# Task_2021-05-29.net
KiCad netlist of a schematic drawn in EasyEDA
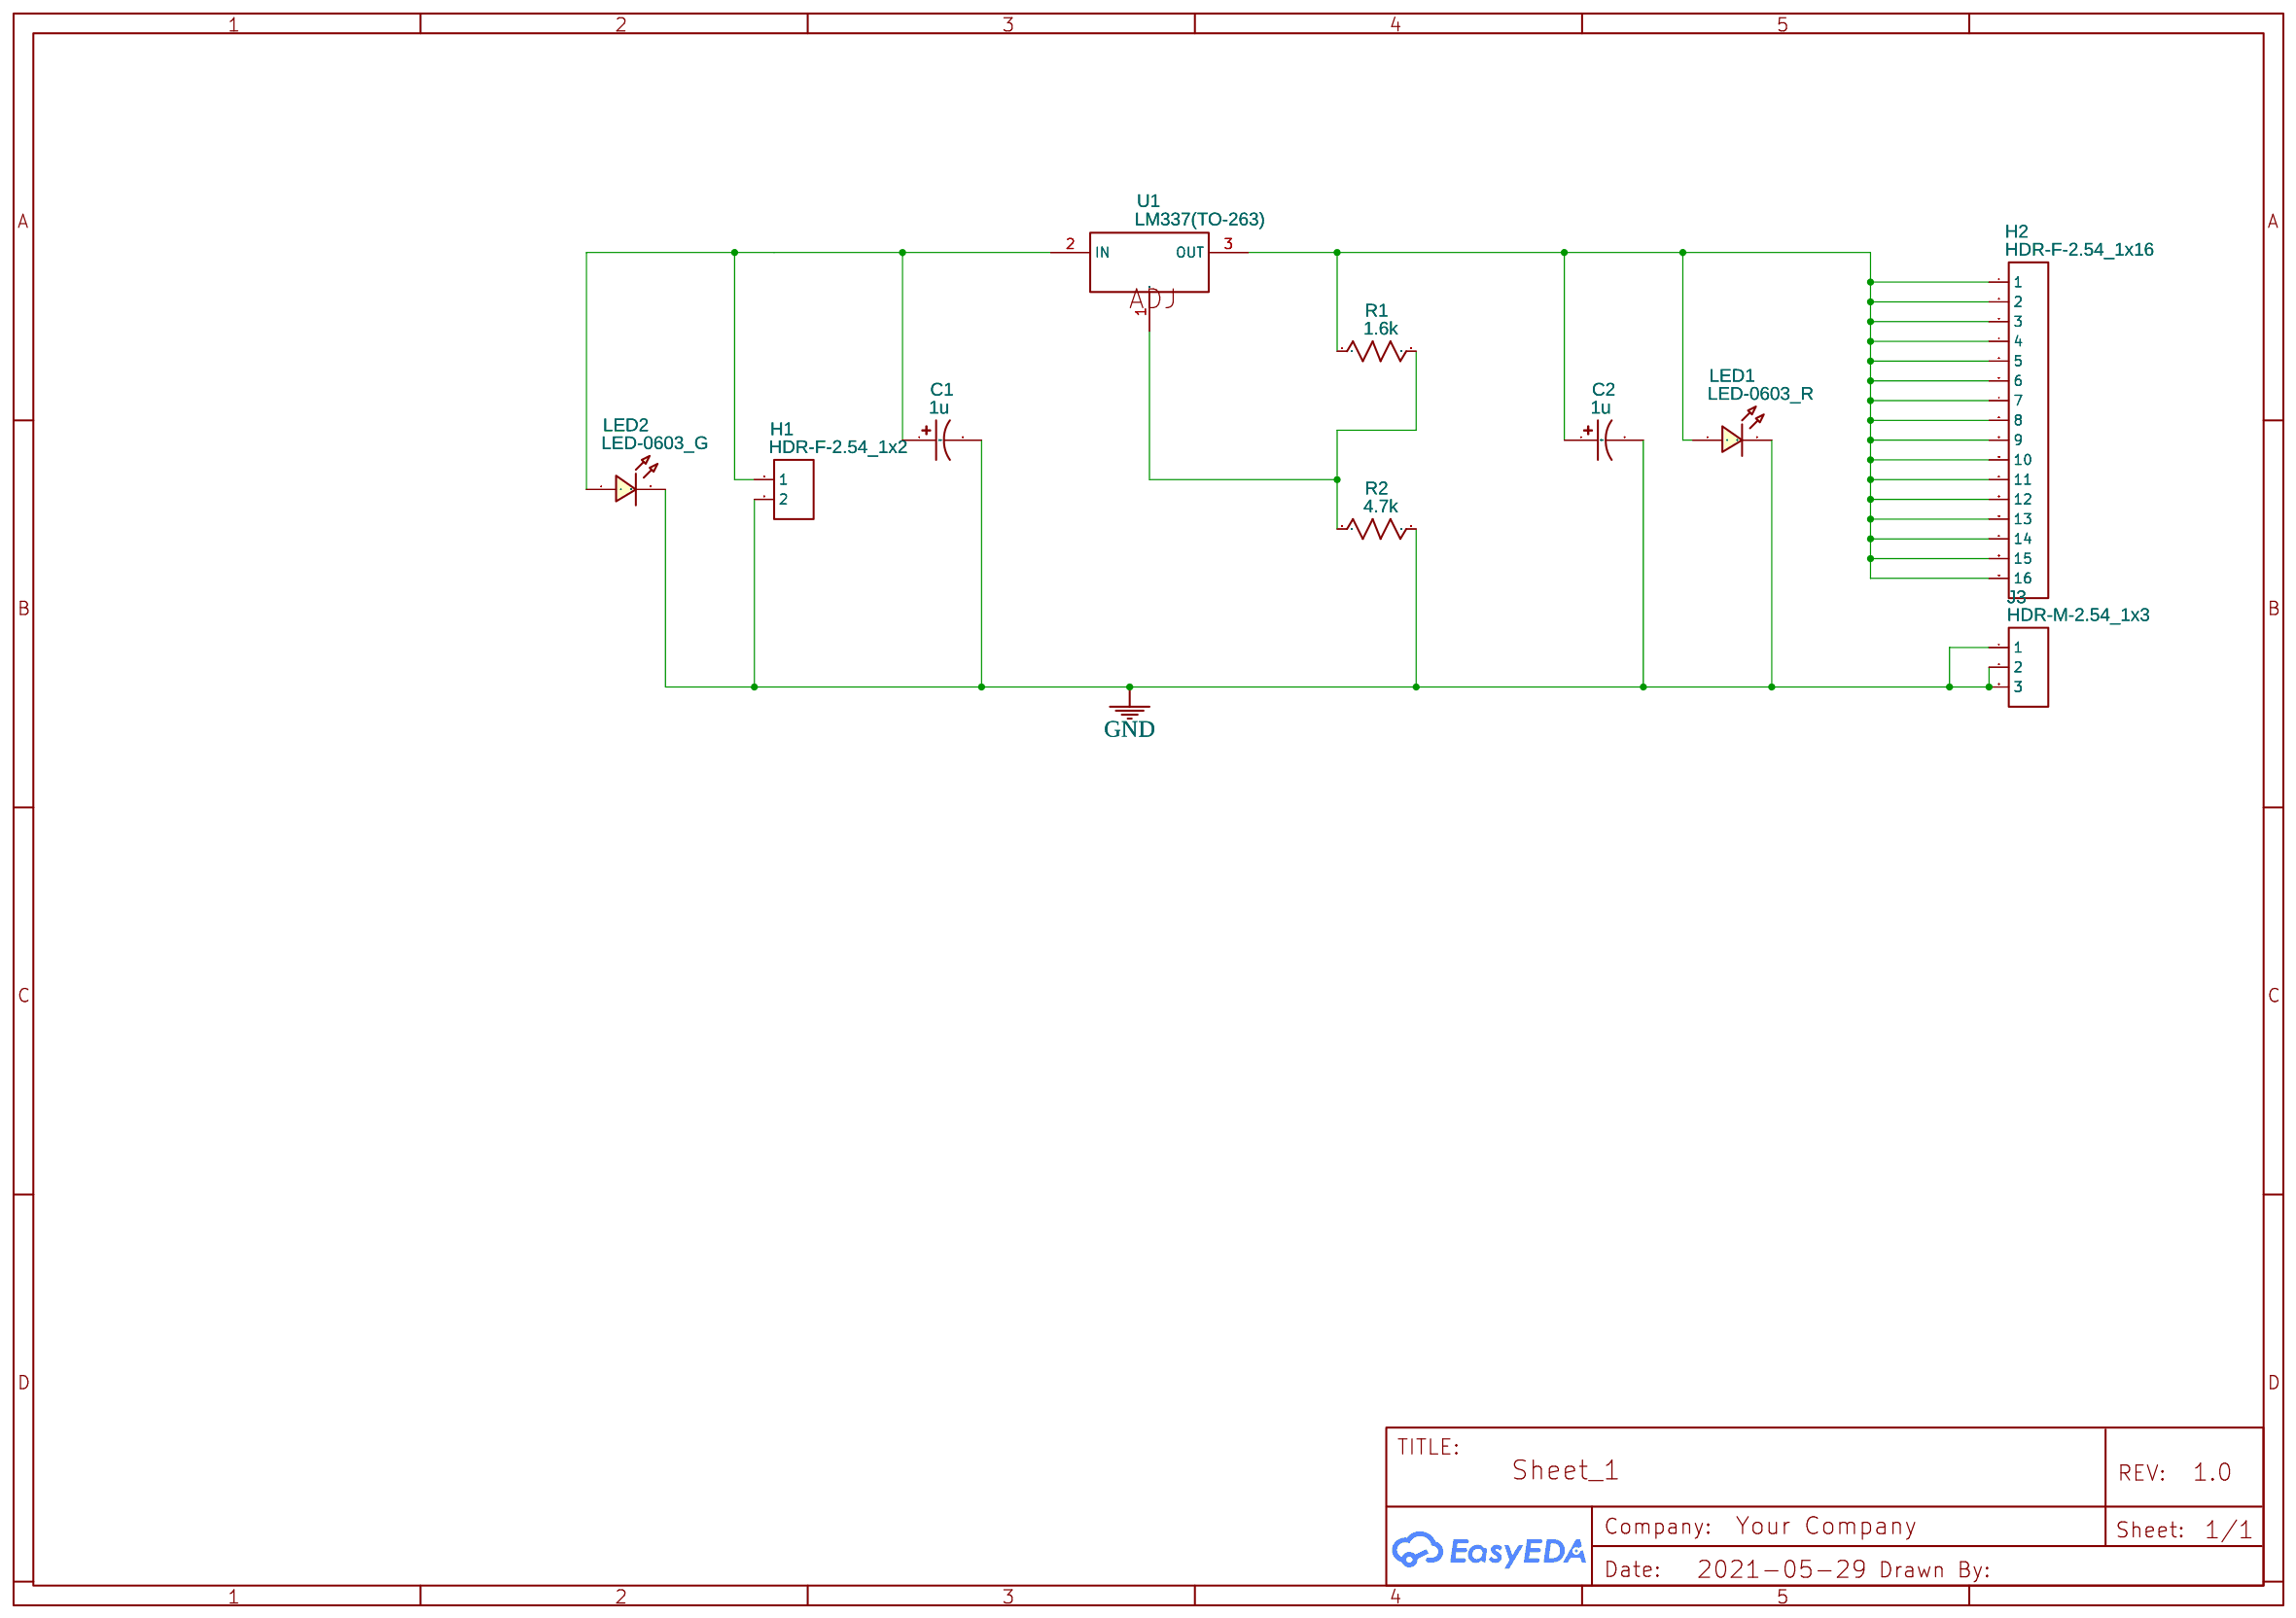
[diagram p0: schematic sheet]

(export (version "E")
  (design (tool "Eeschema 10.0.6"))
  (components
    (comp (ref "C1") (value "1u") (libsource (lib "") (part "C_Tan_SMD_A_US")))
    (comp (ref "C2") (value "1u") (libsource (lib "") (part "C_Tan_SMD_A_US")))
    (comp (ref "H1")
      (value "HDR-F-2.54_1x2")
      (fields (field (name "BOM_Supplier Part") "C49661"))
      (libsource (lib "") (part "HDR-F-2.54_1x2"))
    )
    (comp (ref "H2")
      (value "HDR-F-2.54_1x16")
      (fields (field (name "BOM_Supplier Part") "C66987"))
      (libsource (lib "") (part "HDR-F-2.54_1x16"))
    )
    (comp (ref "J3")
      (value "HDR-M-2.54_1x3")
      (fields (field (name "BOM_Supplier Part") "C180248"))
      (libsource (lib "") (part "HDR-M-2.54_1x3"))
    )
    (comp (ref "LED1")
      (value "LED-0603_R")
      (fields
        (field (name "BOM_Manufacturer Part") "19-217/R6C-AL1M2VY/3T")
        (field (name "BOM_Supplier Part") "C72044")
      )
      (libsource (lib "") (part "LED-0603_R"))
    )
    (comp (ref "LED2")
      (value "LED-0603_G")
      (fields
        (field (name "BOM_Manufacturer Part") "19-217/GHC-YR1S2/3T")
        (field (name "BOM_Supplier Part") "C72043")
      )
      (libsource (lib "") (part "LED-0603_G"))
    )
    (comp (ref "R1") (value "1.6k") (libsource (lib "") (part "R_0603_US")))
    (comp (ref "R2") (value "4.7k") (libsource (lib "") (part "R_0603_US")))
    (comp (ref "U1")
      (value "LM337(TO-263)")
      (fields (field (name "BOM_Manufacturer Part") "LM337D2TG") (field (name "BOM_Supplier Part") "C146782"))
      (libsource (lib "") (part "LM337(TO-263)"))
    )
  )
  (nets
    (net (code "1") (name "GND") (class "Default")
      (node (ref "C1") (pin "2") (pinfunction "2_2") (pintype "unspecified"))
      (node (ref "C2") (pin "2") (pinfunction "2_2") (pintype "unspecified"))
      (node (ref "H1") (pin "2") (pinfunction "2_2") (pintype "input"))
      (node (ref "J3") (pin "1") (pinfunction "1_1") (pintype "input"))
      (node (ref "J3") (pin "2") (pinfunction "2_2") (pintype "input"))
      (node (ref "J3") (pin "3") (pinfunction "3_3") (pintype "input"))
      (node (ref "LED1") (pin "2") (pinfunction "2_2") (pintype "unspecified"))
      (node (ref "LED2") (pin "2") (pinfunction "2_2") (pintype "unspecified"))
      (node (ref "R2") (pin "2") (pinfunction "2_2") (pintype "unspecified"))
    )
    (net (code "2") (name "Net-(U1-ADJ)") (class "Default")
      (node (ref "R1") (pin "2") (pinfunction "2_2") (pintype "unspecified"))
      (node (ref "R2") (pin "1") (pinfunction "1_1") (pintype "unspecified"))
      (node (ref "U1") (pin "1") (pinfunction "ADJ_1") (pintype "passive"))
    )
    (net (code "3") (name "Net-(U1-IN)") (class "Default")
      (node (ref "C1") (pin "1") (pinfunction "1_1") (pintype "unspecified"))
      (node (ref "H1") (pin "1") (pinfunction "1_1") (pintype "input"))
      (node (ref "LED2") (pin "1") (pinfunction "1_1") (pintype "unspecified"))
      (node (ref "U1") (pin "2") (pinfunction "IN_2") (pintype "passive"))
    )
    (net (code "4") (name "Net-(U1-OUT)") (class "Default")
      (node (ref "C2") (pin "1") (pinfunction "1_1") (pintype "unspecified"))
      (node (ref "H2") (pin "1") (pinfunction "1_1") (pintype "unspecified"))
      (node (ref "H2") (pin "10") (pinfunction "10_10") (pintype "unspecified"))
      (node (ref "H2") (pin "11") (pinfunction "11_11") (pintype "unspecified"))
      (node (ref "H2") (pin "12") (pinfunction "12_12") (pintype "unspecified"))
      (node (ref "H2") (pin "13") (pinfunction "13_13") (pintype "unspecified"))
      (node (ref "H2") (pin "14") (pinfunction "14_14") (pintype "unspecified"))
      (node (ref "H2") (pin "15") (pinfunction "15_15") (pintype "unspecified"))
      (node (ref "H2") (pin "16") (pinfunction "16_16") (pintype "unspecified"))
      (node (ref "H2") (pin "2") (pinfunction "2_2") (pintype "unspecified"))
      (node (ref "H2") (pin "3") (pinfunction "3_3") (pintype "unspecified"))
      (node (ref "H2") (pin "4") (pinfunction "4_4") (pintype "unspecified"))
      (node (ref "H2") (pin "5") (pinfunction "5_5") (pintype "unspecified"))
      (node (ref "H2") (pin "6") (pinfunction "6_6") (pintype "unspecified"))
      (node (ref "H2") (pin "7") (pinfunction "7_7") (pintype "unspecified"))
      (node (ref "H2") (pin "8") (pinfunction "8_8") (pintype "unspecified"))
      (node (ref "H2") (pin "9") (pinfunction "9_9") (pintype "unspecified"))
      (node (ref "LED1") (pin "1") (pinfunction "1_1") (pintype "unspecified"))
      (node (ref "R1") (pin "1") (pinfunction "1_1") (pintype "unspecified"))
      (node (ref "U1") (pin "3") (pinfunction "OUT_3") (pintype "passive"))
    )
  )
)
